# UART_ISO.net
KiCad netlist of a schematic drawn in Altium Designer
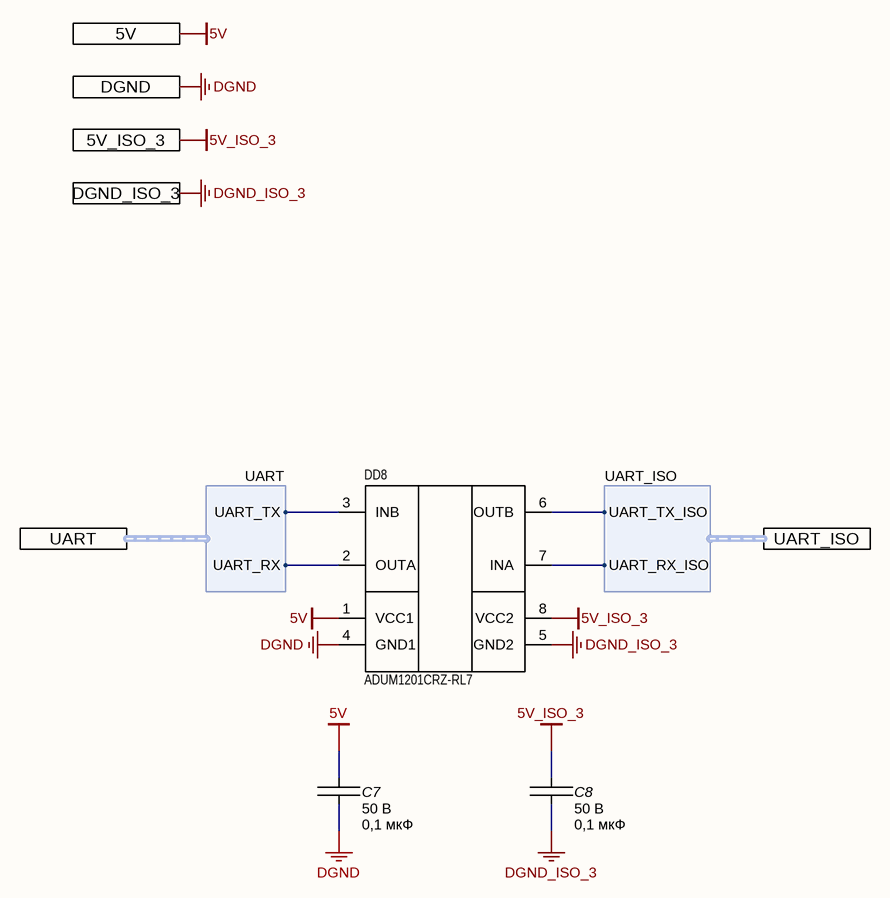
[diagram p0: UART_ISO.SchDoc]

(export (version "E")
  (design (tool "Eeschema 10.0.6"))
  (components
    (comp (ref "C7")
      (value "0,1 мкФ")
      (footprint "C0603C")
      (description "SMD 0603 ; X7R; 0,1 мкФ; 50 В")
      (fields
        (field (name "PART NUMBER") "CC0603KRX7R9BB104")
        (field (name "MANUFACTURER") "YAGEO")
        (field (name "VOLTAGE") "50 В")
      )
      (libsource (lib "Capacitors") (part "CC0603KRX7R9BB104"))
    )
    (comp (ref "C8")
      (value "0,1 мкФ")
      (footprint "C0603C")
      (description "SMD 0603 ; X7R; 0,1 мкФ; 50 В")
      (fields
        (field (name "PART NUMBER") "CC0603KRX7R9BB104")
        (field (name "MANUFACTURER") "YAGEO")
        (field (name "VOLTAGE") "50 В")
      )
      (libsource (lib "Capacitors") (part "CC0603KRX7R9BB104"))
    )
    (comp (ref "DD8")
      (value "ADUM1201CRZ-RL7")
      (footprint "SOIC-8")
      (description "Цифровой изолятор 2.5кВ, 2 канала, 1/1")
      (libsource (lib "ADUM1201CRZ-RL7") (part "ADUM1201CRZ-RL7"))
    )
  )
  (nets
    (net (code "3") (name "/UART_RX") (class "Default")
      (node (ref "DD8") (pin "2") (pinfunction "OUTA_2") (pintype "passive"))
    )
    (net (code "4") (name "/UART_RX_ISO") (class "Default")
      (node (ref "DD8") (pin "7") (pinfunction "INA_7") (pintype "passive"))
    )
    (net (code "5") (name "/UART_TX") (class "Default")
      (node (ref "DD8") (pin "3") (pinfunction "INB_3") (pintype "passive"))
    )
    (net (code "6") (name "/UART_TX_ISO") (class "Default")
      (node (ref "DD8") (pin "6") (pinfunction "OUTB_6") (pintype "passive"))
    )
    (net (code "9") (name "5V") (class "Default")
      (node (ref "C7") (pin "1") (pinfunction "1_1") (pintype "passive"))
      (node (ref "DD8") (pin "1") (pinfunction "VCC1_1") (pintype "passive"))
    )
    (net (code "10") (name "5V_ISO_3") (class "Default")
      (node (ref "C8") (pin "1") (pinfunction "1_1") (pintype "passive"))
      (node (ref "DD8") (pin "8") (pinfunction "VCC2_8") (pintype "passive"))
    )
    (net (code "11") (name "DGND") (class "Default")
      (node (ref "C7") (pin "2") (pinfunction "2_2") (pintype "passive"))
      (node (ref "DD8") (pin "4") (pinfunction "GND1_4") (pintype "passive"))
    )
    (net (code "12") (name "DGND_ISO_3") (class "Default")
      (node (ref "C8") (pin "2") (pinfunction "2_2") (pintype "passive"))
      (node (ref "DD8") (pin "5") (pinfunction "GND2_5") (pintype "passive"))
    )
  )
)
